# LAN9254_D_P1.net
KiCad netlist of a schematic drawn in Altium Designer
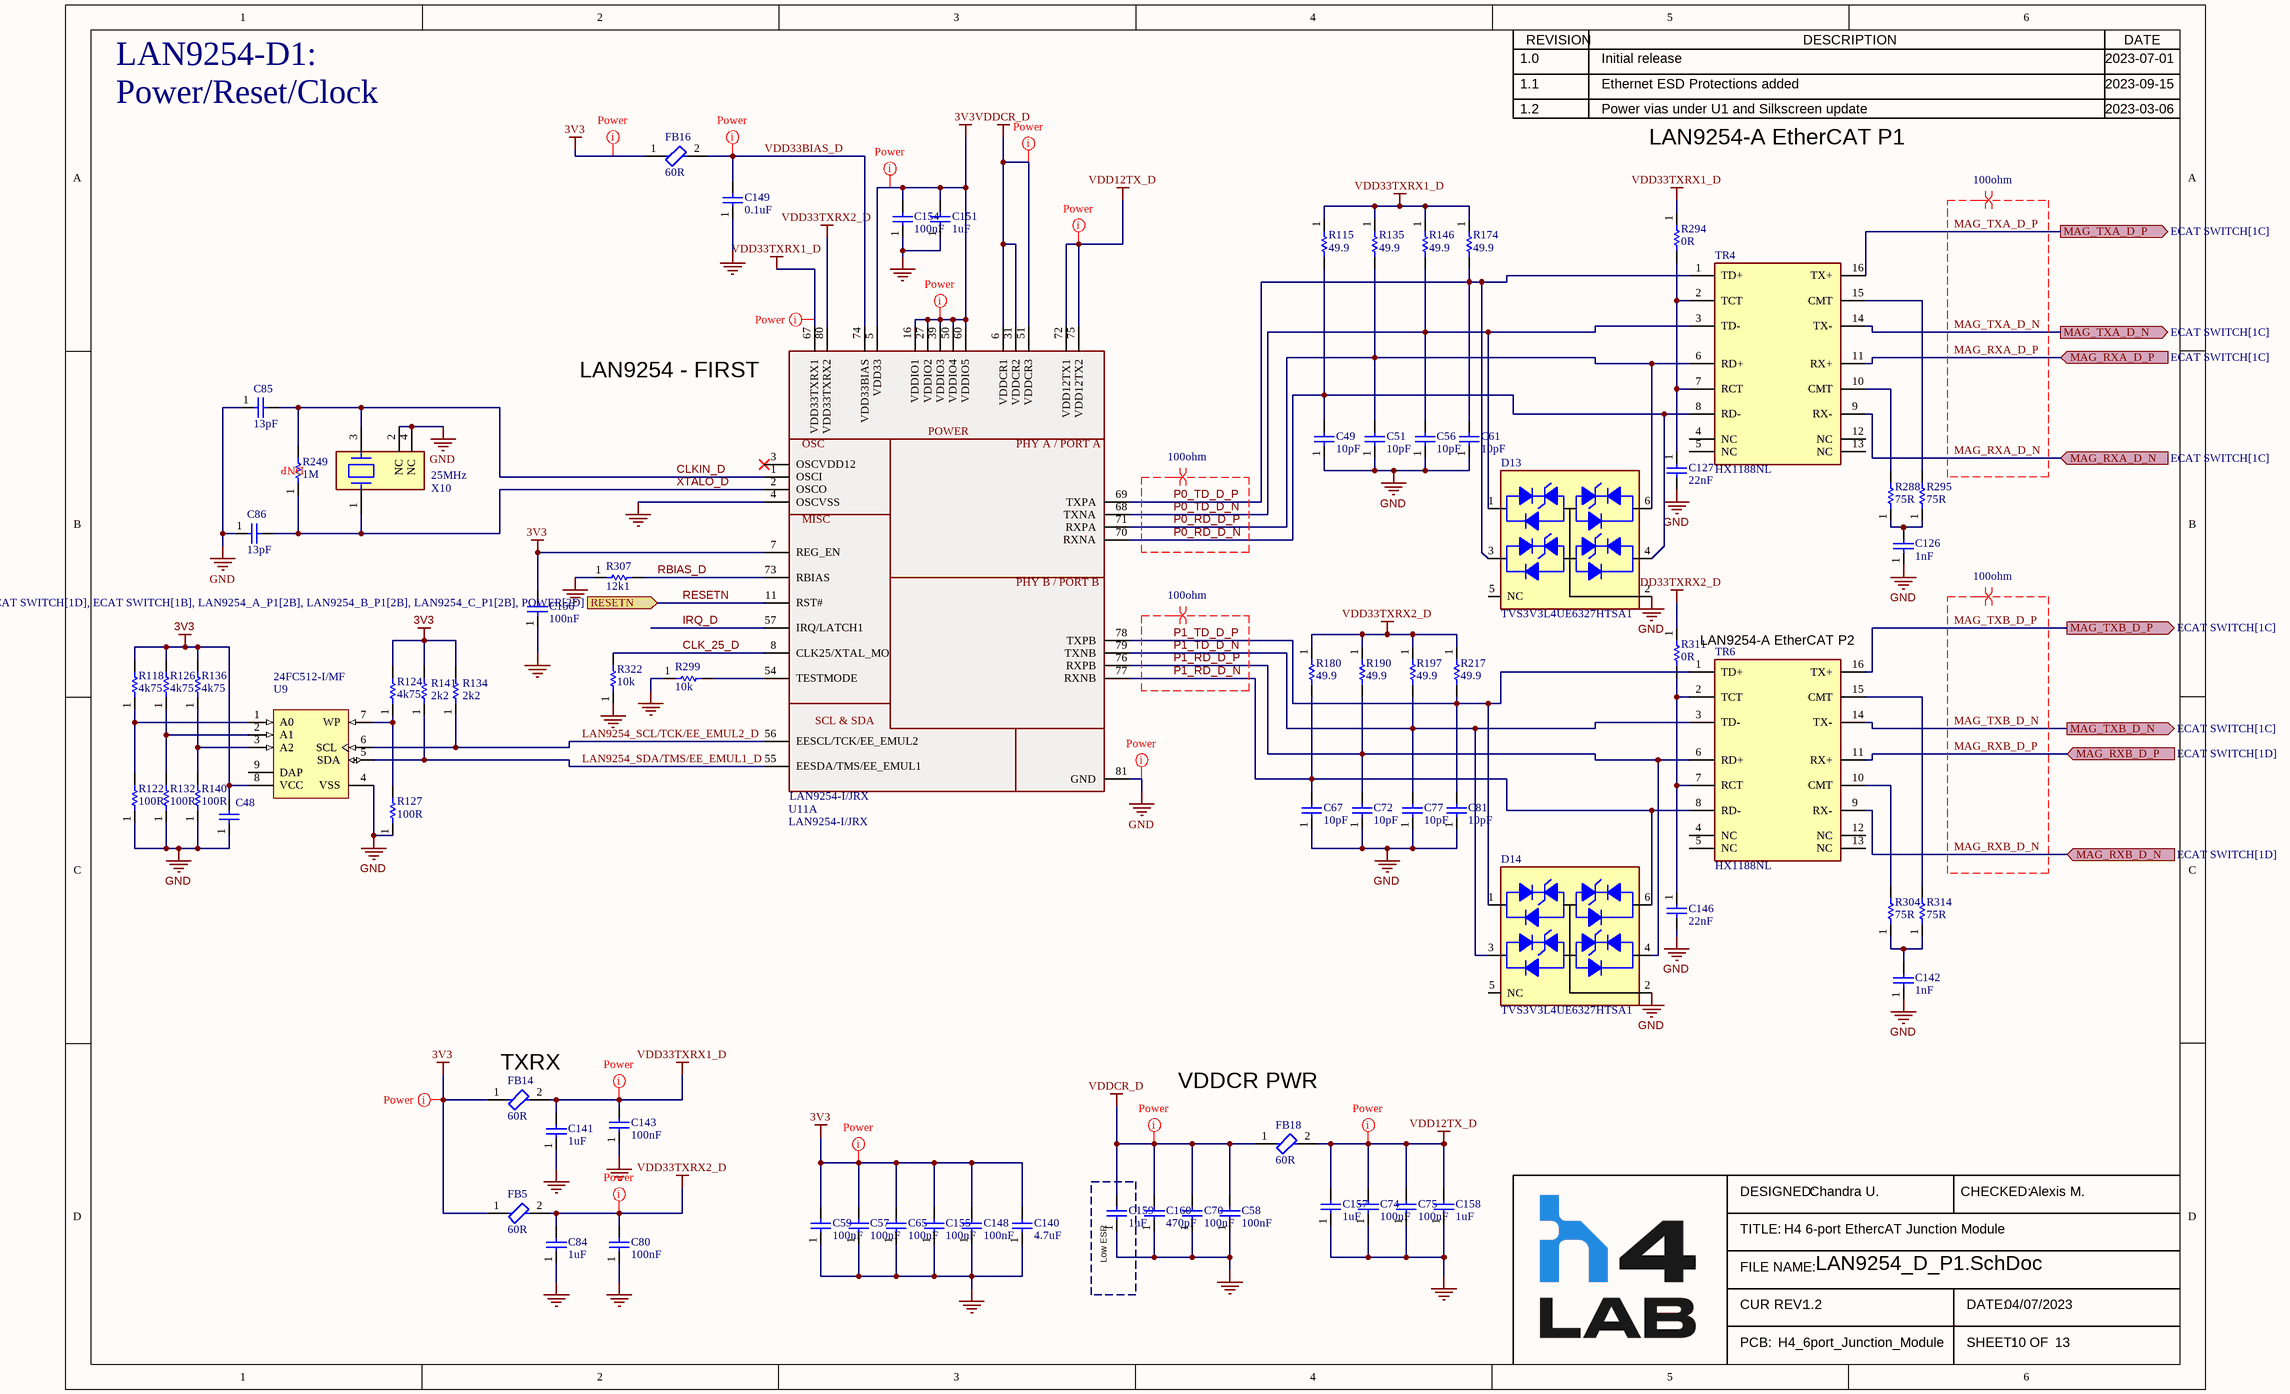
[diagram p0: LAN9254_D_P1.SchDoc]

(export (version "E")
  (design (tool "Eeschema 10.0.6"))
  (components
    (comp (ref "C48")
      (value "GRM155R71C104JA88D")
      (footprint "CAPC1005X03N(0402)")
      (description "CAP CER 0.1UF 16V X7R 0402")
      (fields (field (name "TOLERANCE") "5%"))
      (libsource (lib "IHMC_Altium_Lib") (part "100nF_16V_0402_CAP"))
    )
    (comp (ref "C49")
      (value "10pF")
      (footprint "0402_C")
      (description "Cap Ceramic 10pF 50V C0G 5% SMD 0402 125°C Punched Paper T/R")
      (fields (field (name "TOLERANCE") "5%") (field (name "MANUFACTURER") "KEMET"))
      (libsource (lib "IHMC_Altium_Lib") (part "10pF_50V_0402_C0402C100J5GAC7411"))
    )
    (comp (ref "C51")
      (value "10pF")
      (footprint "0402_C")
      (description "Cap Ceramic 10pF 50V C0G 5% SMD 0402 125°C Punched Paper T/R")
      (fields (field (name "TOLERANCE") "5%") (field (name "MANUFACTURER") "KEMET"))
      (libsource (lib "IHMC_Altium_Lib") (part "10pF_50V_0402_C0402C100J5GAC7411"))
    )
    (comp (ref "C56")
      (value "10pF")
      (footprint "0402_C")
      (description "Cap Ceramic 10pF 50V C0G 5% SMD 0402 125°C Punched Paper T/R")
      (fields (field (name "TOLERANCE") "5%") (field (name "MANUFACTURER") "KEMET"))
      (libsource (lib "IHMC_Altium_Lib") (part "10pF_50V_0402_C0402C100J5GAC7411"))
    )
    (comp (ref "C57")
      (value "100nF")
      (footprint "CAPC1005X03N(0402)")
      (description "CAP CER 0.1UF 16V X7R 0402")
      (fields (field (name "MPN") "GRM155R71C104JA88D") (field (name "TOLERANCE") "5%"))
      (libsource (lib "IHMC_Altium_Lib") (part "100nF_16V_0402_CAP"))
    )
    (comp (ref "C58")
      (value "100nF")
      (footprint "CAPC1005X03N(0402)")
      (description "CAP CER 0.1UF 16V X7R 0402")
      (fields (field (name "MPN") "GRM155R71C104JA88D") (field (name "TOLERANCE") "5%"))
      (libsource (lib "IHMC_Altium_Lib") (part "100nF_16V_0402_CAP"))
    )
    (comp (ref "C59")
      (value "100nF")
      (footprint "CAPC1005X03N(0402)")
      (description "CAP CER 0.1UF 16V X7R 0402")
      (fields (field (name "MPN") "GRM155R71C104JA88D") (field (name "TOLERANCE") "5%"))
      (libsource (lib "IHMC_Altium_Lib") (part "100nF_16V_0402_CAP"))
    )
    (comp (ref "C61")
      (value "10pF")
      (footprint "0402_C")
      (description "Cap Ceramic 10pF 50V C0G 5% SMD 0402 125°C Punched Paper T/R")
      (fields (field (name "TOLERANCE") "5%") (field (name "MANUFACTURER") "KEMET"))
      (libsource (lib "IHMC_Altium_Lib") (part "10pF_50V_0402_C0402C100J5GAC7411"))
    )
    (comp (ref "C65")
      (value "100nF")
      (footprint "CAPC1005X03N(0402)")
      (description "CAP CER 0.1UF 16V X7R 0402")
      (fields (field (name "MPN") "GRM155R71C104JA88D") (field (name "TOLERANCE") "5%"))
      (libsource (lib "IHMC_Altium_Lib") (part "100nF_16V_0402_CAP"))
    )
    (comp (ref "C67")
      (value "10pF")
      (footprint "0402_C")
      (description "Cap Ceramic 10pF 50V C0G 5% SMD 0402 125°C Punched Paper T/R")
      (fields (field (name "TOLERANCE") "5%") (field (name "MANUFACTURER") "KEMET"))
      (libsource (lib "IHMC_Altium_Lib") (part "10pF_50V_0402_C0402C100J5GAC7411"))
    )
    (comp (ref "C70")
      (value "100nF")
      (footprint "CAPC1005X03N(0402)")
      (description "CAP CER 0.1UF 16V X7R 0402")
      (fields (field (name "MPN") "GRM155R71C104JA88D") (field (name "TOLERANCE") "5%"))
      (libsource (lib "IHMC_Altium_Lib") (part "100nF_16V_0402_CAP"))
    )
    (comp (ref "C72")
      (value "10pF")
      (footprint "0402_C")
      (description "Cap Ceramic 10pF 50V C0G 5% SMD 0402 125°C Punched Paper T/R")
      (fields (field (name "TOLERANCE") "5%") (field (name "MANUFACTURER") "KEMET"))
      (libsource (lib "IHMC_Altium_Lib") (part "10pF_50V_0402_C0402C100J5GAC7411"))
    )
    (comp (ref "C74")
      (value "100nF")
      (footprint "CAPC1005X03N(0402)")
      (description "CAP CER 0.1UF 16V X7R 0402")
      (fields (field (name "MPN") "GRM155R71C104JA88D") (field (name "TOLERANCE") "5%"))
      (libsource (lib "IHMC_Altium_Lib") (part "100nF_16V_0402_CAP"))
    )
    (comp (ref "C75")
      (value "100nF")
      (footprint "CAPC1005X03N(0402)")
      (description "CAP CER 0.1UF 16V X7R 0402")
      (fields (field (name "MPN") "GRM155R71C104JA88D") (field (name "TOLERANCE") "5%"))
      (libsource (lib "IHMC_Altium_Lib") (part "100nF_16V_0402_CAP"))
    )
    (comp (ref "C77")
      (value "10pF")
      (footprint "0402_C")
      (description "Cap Ceramic 10pF 50V C0G 5% SMD 0402 125°C Punched Paper T/R")
      (fields (field (name "TOLERANCE") "5%") (field (name "MANUFACTURER") "KEMET"))
      (libsource (lib "IHMC_Altium_Lib") (part "10pF_50V_0402_C0402C100J5GAC7411"))
    )
    (comp (ref "C80")
      (value "100nF")
      (footprint "CAPC1005X03N(0402)")
      (description "CAP CER 0.1UF 16V X7R 0402")
      (fields (field (name "MPN") "GRM155R71C104JA88D") (field (name "TOLERANCE") "5%"))
      (libsource (lib "IHMC_Altium_Lib") (part "100nF_16V_0402_CAP"))
    )
    (comp (ref "C81")
      (value "10pF")
      (footprint "0402_C")
      (description "Cap Ceramic 10pF 50V C0G 5% SMD 0402 125°C Punched Paper T/R")
      (fields (field (name "TOLERANCE") "5%") (field (name "MANUFACTURER") "KEMET"))
      (libsource (lib "IHMC_Altium_Lib") (part "10pF_50V_0402_C0402C100J5GAC7411"))
    )
    (comp (ref "C84")
      (value "1uF")
      (footprint "CAPC1608X09N(0603)")
      (description "MLCC - SMD/SMT 25volts 1uF X5R 10%")
      (fields
        (field (name "MPN") "C0603C105K3PACTU")
        (field (name "VOLTAGE") "25VDC")
        (field (name "DRAWN BY") "TC")
      )
      (libsource (lib "IHMC_Altium_Lib") (part "1uF_25VDC_0603_Cap"))
    )
    (comp (ref "C85")
      (value "13pF")
      (footprint "0402_C")
      (description "Cap Ceramic Monolithic 13pF 50VDC 2% SMD Emboss T/R")
      (fields
        (field (name "MANUFACTURER") "Murata")
        (field (name "MANUFACTURER PART NUMBER") "GRM0225C1H130GA03L")
      )
      (libsource (lib "IHMC_Capacitors") (part "13pF_50V_0402_CAP_GRM0225C1H130GA03L"))
    )
    (comp (ref "C86")
      (value "13pF")
      (footprint "0402_C")
      (description "Cap Ceramic Monolithic 13pF 50VDC 2% SMD Emboss T/R")
      (fields
        (field (name "MANUFACTURER") "Murata")
        (field (name "MANUFACTURER PART NUMBER") "GRM0225C1H130GA03L")
      )
      (libsource (lib "IHMC_Capacitors") (part "13pF_50V_0402_CAP_GRM0225C1H130GA03L"))
    )
    (comp (ref "C126")
      (value "1nF")
      (footprint "CAPC3216X16N(1206)")
      (description "CAP CER 1000PF 2KV X7R 1206")
      (fields (field (name "TOLERANCE") "10%") (field (name "MPN") "CC1206KKX7RDBB102"))
      (libsource (lib "IHMC_Altium_Lib") (part "1nF_2kV_1206_CAP"))
    )
    (comp (ref "C127")
      (value "22nF")
      (footprint "CAPC1005X03N(0402)")
      (description "CAP CER 0.022UF 50V X7R 0402")
      (fields (field (name "MPN") "GCM155R71H223KA55D") (field (name "TOLERANCE") "10%"))
      (libsource (lib "IHMC_Capacitors") (part "22nF_50V_0402_CAP"))
    )
    (comp (ref "C140")
      (value "4.7uF")
      (footprint "CAPC3216X16N(1206)")
      (description "CAP CER 4.7UF 50V X7R 1206")
      (fields (field (name "MPN") "CL31B475KBHNNNE") (field (name "TOLERANCE") "10%"))
      (libsource (lib "IHMC_Altium_Lib") (part "4.7uF_50V_1206_CAP"))
    )
    (comp (ref "C141")
      (value "1uF")
      (footprint "CAPC1608X09N(0603)")
      (description "MLCC - SMD/SMT 25volts 1uF X5R 10%")
      (fields
        (field (name "MPN") "C0603C105K3PACTU")
        (field (name "VOLTAGE") "25VDC")
        (field (name "DRAWN BY") "TC")
      )
      (libsource (lib "IHMC_Altium_Lib") (part "1uF_25VDC_0603_Cap"))
    )
    (comp (ref "C142")
      (value "1nF")
      (footprint "CAPC3216X16N(1206)")
      (description "CAP CER 1000PF 2KV X7R 1206")
      (fields (field (name "TOLERANCE") "10%") (field (name "MPN") "CC1206KKX7RDBB102"))
      (libsource (lib "IHMC_Altium_Lib") (part "1nF_2kV_1206_CAP"))
    )
    (comp (ref "C143")
      (value "100nF")
      (footprint "CAPC1005X03N(0402)")
      (description "CAP CER 0.1UF 16V X7R 0402")
      (fields (field (name "MPN") "GRM155R71C104JA88D") (field (name "TOLERANCE") "5%"))
      (libsource (lib "IHMC_Altium_Lib") (part "100nF_16V_0402_CAP"))
    )
    (comp (ref "C146")
      (value "22nF")
      (footprint "CAPC1005X03N(0402)")
      (description "CAP CER 0.022UF 50V X7R 0402")
      (fields (field (name "MPN") "GCM155R71H223KA55D") (field (name "TOLERANCE") "10%"))
      (libsource (lib "IHMC_Capacitors") (part "22nF_50V_0402_CAP"))
    )
    (comp (ref "C148")
      (value "100nF")
      (footprint "CAPC1005X03N(0402)")
      (description "CAP CER 0.1UF 16V X7R 0402")
      (fields (field (name "MPN") "GRM155R71C104JA88D") (field (name "TOLERANCE") "5%"))
      (libsource (lib "IHMC_Altium_Lib") (part "100nF_16V_0402_CAP"))
    )
    (comp (ref "C149")
      (value "0.1uF")
      (footprint "CAPC1608X09N(0603)")
      (description "CAP CER 0.1UF 100V X7R 0603")
      (fields (field (name "MPN") "CL10B104KC8NNNC") (field (name "TOLERANCE") "10%"))
      (libsource (lib "IHMC_Altium_Lib") (part "0.1uF_100V_0603_CAP"))
    )
    (comp (ref "C151")
      (value "1uF")
      (footprint "0603_C")
      (description "Multilayer Ceramic Capacitors (High dielectric type), 10V, 1 uF, ± 10 %, 0603, X5R, RoHS")
      (fields (field (name "TOLERANCE") "10%") (field (name "MANUFACTURER") "Taiyo Yuden"))
      (libsource (lib "IHMC_Capacitors") (part "1uF_10V_low_ESR_0603_LMK107BJ105KA-T"))
    )
    (comp (ref "C154")
      (value "100nF")
      (footprint "CAPC1005X03N(0402)")
      (description "CAP CER 0.1UF 16V X7R 0402")
      (fields (field (name "MPN") "GRM155R71C104JA88D") (field (name "TOLERANCE") "5%"))
      (libsource (lib "IHMC_Altium_Lib") (part "100nF_16V_0402_CAP"))
    )
    (comp (ref "C155")
      (value "100nF")
      (footprint "CAPC1005X03N(0402)")
      (description "CAP CER 0.1UF 16V X7R 0402")
      (fields (field (name "MPN") "GRM155R71C104JA88D") (field (name "TOLERANCE") "5%"))
      (libsource (lib "IHMC_Altium_Lib") (part "100nF_16V_0402_CAP"))
    )
    (comp (ref "C156")
      (value "100nF")
      (footprint "CAPC1005X03N(0402)")
      (description "CAP CER 0.1UF 16V X7R 0402")
      (fields (field (name "MPN") "GRM155R71C104JA88D") (field (name "TOLERANCE") "5%"))
      (libsource (lib "IHMC_Altium_Lib") (part "100nF_16V_0402_CAP"))
    )
    (comp (ref "C157")
      (value "1uF")
      (footprint "CAPC1608X09N(0603)")
      (description "MLCC - SMD/SMT 25volts 1uF X5R 10%")
      (fields
        (field (name "MPN") "C0603C105K3PACTU")
        (field (name "VOLTAGE") "25VDC")
        (field (name "DRAWN BY") "TC")
      )
      (libsource (lib "IHMC_Altium_Lib") (part "1uF_25VDC_0603_Cap"))
    )
    (comp (ref "C158")
      (value "1uF")
      (footprint "CAPC1608X09N(0603)")
      (description "MLCC - SMD/SMT 25volts 1uF X5R 10%")
      (fields
        (field (name "MPN") "C0603C105K3PACTU")
        (field (name "VOLTAGE") "25VDC")
        (field (name "DRAWN BY") "TC")
      )
      (libsource (lib "IHMC_Altium_Lib") (part "1uF_25VDC_0603_Cap"))
    )
    (comp (ref "C159")
      (value "1uF")
      (footprint "0603_C")
      (description "Multilayer Ceramic Capacitors (High dielectric type), 10V, 1 uF, ± 10 %, 0603, X5R, RoHS")
      (fields (field (name "TOLERANCE") "10%") (field (name "MANUFACTURER") "Taiyo Yuden"))
      (libsource (lib "IHMC_Capacitors") (part "1uF_10V_low_ESR_0603_LMK107BJ105KA-T"))
    )
    (comp (ref "C160")
      (value "470pF")
      (footprint "CAPC1005X03N(0402)")
      (description "CAP CER 470PF 50V C0G/NP0 0402")
      (fields (field (name "MPN") "GCM1555C1H471JA16D") (field (name "VOLTAGE") "50V"))
      (libsource (lib "IHMC_Altium_Lib") (part "470pF_50V_0402_CAP"))
    )
    (comp (ref "D13")
      (value "TVS3V3L4UE6327HTSA1")
      (footprint "FP-SOT457-MFG")
      (description "Trans Voltage Suppressor Diode, 3.3V V(RWM), Unidirectional, 4 Element, Silicon")
      (fields (field (name "MANUFACTURER") "Infineon"))
      (libsource (lib "IHMC_Altium_Lib") (part "TVS_DIODE_ETHERCAT_PHY_7.7V_20A_TVS3V3L4UE6327HTSA1"))
    )
    (comp (ref "D14")
      (value "TVS3V3L4UE6327HTSA1")
      (footprint "FP-SOT457-MFG")
      (description "Trans Voltage Suppressor Diode, 3.3V V(RWM), Unidirectional, 4 Element, Silicon")
      (fields (field (name "MANUFACTURER") "Infineon"))
      (libsource (lib "IHMC_Altium_Lib") (part "TVS_DIODE_ETHERCAT_PHY_7.7V_20A_TVS3V3L4UE6327HTSA1"))
    )
    (comp (ref "FB5")
      (value "BKP2125HS600-T")
      (footprint "FP-BKP2125-IPC_C")
      (fields
        (field (name "TOLERANCE") "25%")
        (field (name "MANUFACTURER") "Taiyo Yuden")
        (field (name "IMPEDANCE") "60R")
      )
      (libsource (lib "IHMC_Altium_Lib") (part "60R_100Mhz_0805_3A"))
    )
    (comp (ref "FB14")
      (value "BKP2125HS600-T")
      (footprint "FP-BKP2125-IPC_C")
      (fields
        (field (name "TOLERANCE") "25%")
        (field (name "MANUFACTURER") "Taiyo Yuden")
        (field (name "IMPEDANCE") "60R")
      )
      (libsource (lib "IHMC_Altium_Lib") (part "60R_100Mhz_0805_3A"))
    )
    (comp (ref "FB16")
      (value "BKP2125HS600-T")
      (footprint "FP-BKP2125-IPC_C")
      (fields
        (field (name "TOLERANCE") "25%")
        (field (name "MANUFACTURER") "Taiyo Yuden")
        (field (name "IMPEDANCE") "60R")
      )
      (libsource (lib "IHMC_Altium_Lib") (part "60R_100Mhz_0805_3A"))
    )
    (comp (ref "FB18")
      (value "BKP2125HS600-T")
      (footprint "FP-BKP2125-IPC_C")
      (fields
        (field (name "TOLERANCE") "25%")
        (field (name "MANUFACTURER") "Taiyo Yuden")
        (field (name "IMPEDANCE") "60R")
      )
      (libsource (lib "IHMC_Altium_Lib") (part "60R_100Mhz_0805_3A"))
    )
    (comp (ref "R115")
      (value "49.9")
      (footprint "RESC1005X06N(0402)")
      (description "RES SMD 49.9 OHM 1% 1/16W 0402")
      (fields
        (field (name "MPN") "CRCW040249R9FKED")
        (field (name "TOLERANCE") "1%")
        (field (name "DRAWN BY") "TC")
      )
      (libsource (lib "IHMC_Altium_Lib") (part "49R9_1/10W_0402_RES"))
    )
    (comp (ref "R118")
      (value "4k75")
      (footprint "RESC1005X06N(0402)")
      (description "RES SMD 4.75K OHM 1% 1/16W 0402")
      (fields (field (name "MPN") "RC0402FR-074K75L") (field (name "POWER") "1/16"))
      (libsource (lib "IHMC_Altium_Lib") (part "4k75_1/16_0402_RES"))
    )
    (comp (ref "R122")
      (value "100R")
      (footprint "0402")
      (description "Res Thick Film 0402 100 Ohm 1% 0.063W(1/16W) ±200ppm/C Pad SMD Automotive T/R")
      (fields
        (field (name "MANUFACTURER") "TE Connectivity")
        (field (name "MANUFACTURER PART NUMBER") "CRGCQ0402F100R")
      )
      (libsource (lib "IHMC_Altium_Lib") (part "100R_1/16_0402_RES"))
    )
    (comp (ref "R124")
      (value "4k75")
      (footprint "RESC1005X06N(0402)")
      (description "RES SMD 4.75K OHM 1% 1/16W 0402")
      (fields (field (name "MPN") "RC0402FR-074K75L") (field (name "POWER") "1/16"))
      (libsource (lib "IHMC_Altium_Lib") (part "4k75_1/16_0402_RES"))
    )
    (comp (ref "R126")
      (value "4k75")
      (footprint "RESC1005X06N(0402)")
      (description "RES SMD 4.75K OHM 1% 1/16W 0402")
      (fields (field (name "MPN") "RC0402FR-074K75L") (field (name "POWER") "1/16"))
      (libsource (lib "IHMC_Altium_Lib") (part "4k75_1/16_0402_RES"))
    )
    (comp (ref "R127")
      (value "100R")
      (footprint "0402")
      (description "Res Thick Film 0402 100 Ohm 1% 0.063W(1/16W) ±200ppm/C Pad SMD Automotive T/R")
      (fields
        (field (name "MANUFACTURER") "TE Connectivity")
        (field (name "MANUFACTURER PART NUMBER") "CRGCQ0402F100R")
      )
      (libsource (lib "IHMC_Altium_Lib") (part "100R_1/16_0402_RES"))
    )
    (comp (ref "R132")
      (value "100R")
      (footprint "0402")
      (description "Res Thick Film 0402 100 Ohm 1% 0.063W(1/16W) ±200ppm/C Pad SMD Automotive T/R")
      (fields
        (field (name "MANUFACTURER") "TE Connectivity")
        (field (name "MANUFACTURER PART NUMBER") "CRGCQ0402F100R")
      )
      (libsource (lib "IHMC_Altium_Lib") (part "100R_1/16_0402_RES"))
    )
    (comp (ref "R134")
      (value "2k2")
      (footprint "0402")
      (description "Vishay CRCW Series Thick Film Resistor 0402 Case 2.2k 5% 0.063W 200ppm/K")
      (fields (field (name "TOLERANCE") "5%") (field (name "MANUFACTURER") "Vishay Dale"))
      (libsource (lib "IHMC_Altium_Lib") (part "2k2_1/16_0402_CRCW04022K20JNED_RES"))
    )
    (comp (ref "R135")
      (value "49.9")
      (footprint "RESC1005X06N(0402)")
      (description "RES SMD 49.9 OHM 1% 1/16W 0402")
      (fields
        (field (name "MPN") "CRCW040249R9FKED")
        (field (name "TOLERANCE") "1%")
        (field (name "DRAWN BY") "TC")
      )
      (libsource (lib "IHMC_Altium_Lib") (part "49R9_1/10W_0402_RES"))
    )
    (comp (ref "R136")
      (value "4k75")
      (footprint "RESC1005X06N(0402)")
      (description "RES SMD 4.75K OHM 1% 1/16W 0402")
      (fields (field (name "MPN") "RC0402FR-074K75L") (field (name "POWER") "1/16"))
      (libsource (lib "IHMC_Altium_Lib") (part "4k75_1/16_0402_RES"))
    )
    (comp (ref "R140")
      (value "100R")
      (footprint "0402")
      (description "Res Thick Film 0402 100 Ohm 1% 0.063W(1/16W) ±200ppm/C Pad SMD Automotive T/R")
      (fields
        (field (name "MANUFACTURER") "TE Connectivity")
        (field (name "MANUFACTURER PART NUMBER") "CRGCQ0402F100R")
      )
      (libsource (lib "IHMC_Altium_Lib") (part "100R_1/16_0402_RES"))
    )
    (comp (ref "R141")
      (value "2k2")
      (footprint "0402")
      (description "Vishay CRCW Series Thick Film Resistor 0402 Case 2.2k 5% 0.063W 200ppm/K")
      (fields (field (name "TOLERANCE") "5%") (field (name "MANUFACTURER") "Vishay Dale"))
      (libsource (lib "IHMC_Altium_Lib") (part "2k2_1/16_0402_CRCW04022K20JNED_RES"))
    )
    (comp (ref "R146")
      (value "49.9")
      (footprint "RESC1005X06N(0402)")
      (description "RES SMD 49.9 OHM 1% 1/16W 0402")
      (fields
        (field (name "MPN") "CRCW040249R9FKED")
        (field (name "TOLERANCE") "1%")
        (field (name "DRAWN BY") "TC")
      )
      (libsource (lib "IHMC_Altium_Lib") (part "49R9_1/10W_0402_RES"))
    )
    (comp (ref "R174")
      (value "49.9")
      (footprint "RESC1005X06N(0402)")
      (description "RES SMD 49.9 OHM 1% 1/16W 0402")
      (fields
        (field (name "MPN") "CRCW040249R9FKED")
        (field (name "TOLERANCE") "1%")
        (field (name "DRAWN BY") "TC")
      )
      (libsource (lib "IHMC_Altium_Lib") (part "49R9_1/10W_0402_RES"))
    )
    (comp (ref "R180")
      (value "49.9")
      (footprint "RESC1005X06N(0402)")
      (description "RES SMD 49.9 OHM 1% 1/16W 0402")
      (fields
        (field (name "MPN") "CRCW040249R9FKED")
        (field (name "TOLERANCE") "1%")
        (field (name "DRAWN BY") "TC")
      )
      (libsource (lib "IHMC_Altium_Lib") (part "49R9_1/10W_0402_RES"))
    )
    (comp (ref "R190")
      (value "49.9")
      (footprint "RESC1005X06N(0402)")
      (description "RES SMD 49.9 OHM 1% 1/16W 0402")
      (fields
        (field (name "MPN") "CRCW040249R9FKED")
        (field (name "TOLERANCE") "1%")
        (field (name "DRAWN BY") "TC")
      )
      (libsource (lib "IHMC_Altium_Lib") (part "49R9_1/10W_0402_RES"))
    )
    (comp (ref "R197")
      (value "49.9")
      (footprint "RESC1005X06N(0402)")
      (description "RES SMD 49.9 OHM 1% 1/16W 0402")
      (fields
        (field (name "MPN") "CRCW040249R9FKED")
        (field (name "TOLERANCE") "1%")
        (field (name "DRAWN BY") "TC")
      )
      (libsource (lib "IHMC_Altium_Lib") (part "49R9_1/10W_0402_RES"))
    )
    (comp (ref "R217")
      (value "49.9")
      (footprint "RESC1005X06N(0402)")
      (description "RES SMD 49.9 OHM 1% 1/16W 0402")
      (fields
        (field (name "MPN") "CRCW040249R9FKED")
        (field (name "TOLERANCE") "1%")
        (field (name "DRAWN BY") "TC")
      )
      (libsource (lib "IHMC_Altium_Lib") (part "49R9_1/10W_0402_RES"))
    )
    (comp (ref "R249")
      (value "1M")
      (footprint "RESC1608X09N(0603)")
      (description "RES SMD 1M OHM 1% 1/10W 0603")
      (fields (field (name "MPN") "RC0603FR-071ML") (field (name "TOLERANCE") "1%"))
      (libsource (lib "IHMC_Altium_Lib") (part "1M_1/10W_RES_0603"))
    )
    (comp (ref "R288")
      (value "75R")
      (footprint "RESC1005X06N(0402)")
      (description "RES SMD 75 OHM 1% 1/16W 0402")
      (fields
        (field (name "MPN") "CRCW040275R0FKEDC")
        (field (name "TOLERANCE") "+/-1%")
        (field (name "DRAWN BY") "TC")
      )
      (libsource (lib "IHMC_Altium_Lib") (part "75R_1/10W_0402_RES"))
    )
    (comp (ref "R294")
      (value "0R")
      (footprint "0402")
      (fields
        (field (name "MANUFACTURER") "Vishay Dale")
        (field (name "MANUFACTURER PART NUMBER") "RCS04020000Z0ED")
      )
      (libsource (lib "IHMC_Altium_Lib") (part "0R_1/5W_0402_RCS04020000Z0ED_RES"))
    )
    (comp (ref "R295")
      (value "75R")
      (footprint "RESC1005X06N(0402)")
      (description "RES SMD 75 OHM 1% 1/16W 0402")
      (fields
        (field (name "MPN") "CRCW040275R0FKEDC")
        (field (name "TOLERANCE") "+/-1%")
        (field (name "DRAWN BY") "TC")
      )
      (libsource (lib "IHMC_Altium_Lib") (part "75R_1/10W_0402_RES"))
    )
    (comp (ref "R299")
      (value "10k")
      (footprint "RESC1005X06N(0402)")
      (description "RES SMD 10K OHM 1% 1/16W 0402")
      (fields (field (name "TOLERANCE") "1%") (field (name "POWER") "1/16W"))
      (libsource (lib "IHMC_Resistors") (part "10k_1/16W_0402_RES"))
    )
    (comp (ref "R304")
      (value "75R")
      (footprint "RESC1005X06N(0402)")
      (description "RES SMD 75 OHM 1% 1/16W 0402")
      (fields
        (field (name "MPN") "CRCW040275R0FKEDC")
        (field (name "TOLERANCE") "+/-1%")
        (field (name "DRAWN BY") "TC")
      )
      (libsource (lib "IHMC_Altium_Lib") (part "75R_1/10W_0402_RES"))
    )
    (comp (ref "R307")
      (value "12k1")
      (footprint "RESC1005X06N(0402)")
      (description "RES SMD 12.1K OHM 1% 1/16W 0402")
      (fields (field (name "MPN") "RC0402FR-0712K1L") (field (name "TOLERANCE") "1%"))
      (libsource (lib "IHMC_Altium_Lib") (part "12k1_1/16W-0402_RES"))
    )
    (comp (ref "R311")
      (value "0R")
      (footprint "0402")
      (fields
        (field (name "MANUFACTURER") "Vishay Dale")
        (field (name "MANUFACTURER PART NUMBER") "RCS04020000Z0ED")
      )
      (libsource (lib "IHMC_Altium_Lib") (part "0R_1/5W_0402_RCS04020000Z0ED_RES"))
    )
    (comp (ref "R314")
      (value "75R")
      (footprint "RESC1005X06N(0402)")
      (description "RES SMD 75 OHM 1% 1/16W 0402")
      (fields
        (field (name "MPN") "CRCW040275R0FKEDC")
        (field (name "TOLERANCE") "+/-1%")
        (field (name "DRAWN BY") "TC")
      )
      (libsource (lib "IHMC_Altium_Lib") (part "75R_1/10W_0402_RES"))
    )
    (comp (ref "R322")
      (value "10k")
      (footprint "RESC1005X06N(0402)")
      (description "RES SMD 10K OHM 1% 1/16W 0402")
      (fields (field (name "TOLERANCE") "1%") (field (name "POWER") "1/16W"))
      (libsource (lib "IHMC_Resistors") (part "10k_1/16W_0402_RES"))
    )
    (comp (ref "TR4")
      (value "HX1188NL")
      (footprint "FP-HX1188NL-MFG")
      (description "Datacom Transformer, GENERAL PURPOSE Application(s), 1:1; 1:1")
      (fields (field (name "MANUFACTURER") "Pulse"))
      (libsource (lib "IHMC_Ethernet") (part "HX1188NL_TRANSFO_LAN_-40-85DEG"))
    )
    (comp (ref "TR6")
      (value "HX1188NL")
      (footprint "FP-HX1188NL-MFG")
      (description "Datacom Transformer, GENERAL PURPOSE Application(s), 1:1; 1:1")
      (fields (field (name "MANUFACTURER") "Pulse"))
      (libsource (lib "IHMC_Ethernet") (part "HX1188NL_TRANSFO_LAN_-40-85DEG"))
    )
    (comp (ref "U9")
      (value "24FC512-I/MF")
      (footprint "DFNS-MF8")
      (description "EEPROM Serial-2Wire 512K-bit 64K x 8 1.8V/2.5V/3.3V/5V 8-Pin DFN-S EP Tube")
      (fields (field (name "MANUFACTURER") "Microchip"))
      (libsource (lib "IHMC_Altium_Lib") (part "EEPROM_512kb_1MHz_24FC512-I/MF"))
    )
    (comp (ref "U11")
      (value "LAN9254-I/JRX")
      (footprint "QFP50P1400X1400X120-81N")
      (description "2/3-PORT Ethercat Slave Controller With 32 Digios With Integrated Ethernet Phys")
      (fields (field (name "MANUFACTURER") "Microchip"))
      (libsource (lib "IHMC_Ethernet") (part "LAN9254-I/JRX"))
    )
    (comp (ref "X10")
      (value "XRCGB25M000F3A00R0")
      (footprint "FP-XRCGB-MFG")
      (description "Crystal 25MHz ±30ppm (Tol) ±35ppm (Stability) 6pF 100Ohm Automotive 4-Pin SMD T/R")
      (fields (field (name "FREQUENCY") "25MHz") (field (name "MANUFACTURER") "Murata"))
      (libsource (lib "IHMC_Altium_Lib") (part "25MHz_Crystal_2016_35PPM_XRCGB25M000F3A00R0"))
    )
  )
  (nets
    (net (code "1") (name "/CLKIN_D") (class "Default")
      (node (ref "C85") (pin "2") (pinfunction "2_2") (pintype "passive"))
      (node (ref "R249") (pin "2") (pinfunction "2_2") (pintype "passive"))
      (node (ref "U11") (pin "1") (pinfunction "OSCI_1") (pintype "passive"))
      (node (ref "X10") (pin "3") (pintype "passive"))
    )
    (net (code "2") (name "/CLK_25_D") (class "Default")
      (node (ref "R322") (pin "2") (pinfunction "2_2") (pintype "passive"))
      (node (ref "U11") (pin "8") (pinfunction "CLK25/XTAL_MO_8") (pintype "passive"))
    )
    (net (code "3") (name "/IRQ_D") (class "Default")
      (node (ref "U11") (pin "57") (pinfunction "IRQ/LATCH1_57") (pintype "passive"))
    )
    (net (code "4") (name "/LAN9254_SCL{slash}TCK{slash}EE_EMUL2_D") (class "Default")
      (node (ref "R134") (pin "1") (pinfunction "1_1") (pintype "passive"))
      (node (ref "U11") (pin "56") (pinfunction "EESCL/TCK/EE_EMUL2_56") (pintype "passive"))
      (node (ref "U9") (pin "6") (pinfunction "SCL_6") (pintype "input"))
    )
    (net (code "5") (name "/LAN9254_SDA{slash}TMS{slash}EE_EMUL1_D") (class "Default")
      (node (ref "R141") (pin "1") (pinfunction "1_1") (pintype "passive"))
      (node (ref "U11") (pin "55") (pinfunction "EESDA/TMS/EE_EMUL1_55") (pintype "passive"))
      (node (ref "U9") (pin "5") (pinfunction "SDA_5") (pintype "bidirectional"))
    )
    (net (code "6") (name "/MAG_RXA_D_N") (class "Default")
      (node (ref "TR4") (pin "9") (pinfunction "RX-_9") (pintype "passive"))
    )
    (net (code "7") (name "/MAG_RXA_D_P") (class "Default")
      (node (ref "TR4") (pin "11") (pinfunction "RX+_11") (pintype "passive"))
    )
    (net (code "8") (name "/MAG_RXB_D_N") (class "Default")
      (node (ref "TR6") (pin "9") (pinfunction "RX-_9") (pintype "passive"))
    )
    (net (code "9") (name "/MAG_RXB_D_P") (class "Default")
      (node (ref "TR6") (pin "11") (pinfunction "RX+_11") (pintype "passive"))
    )
    (net (code "10") (name "/MAG_TXA_D_N") (class "Default")
      (node (ref "TR4") (pin "14") (pinfunction "TX-_14") (pintype "passive"))
    )
    (net (code "11") (name "/MAG_TXA_D_P") (class "Default")
      (node (ref "TR4") (pin "16") (pinfunction "TX+_16") (pintype "passive"))
    )
    (net (code "12") (name "/MAG_TXB_D_N") (class "Default")
      (node (ref "TR6") (pin "14") (pinfunction "TX-_14") (pintype "passive"))
    )
    (net (code "13") (name "/MAG_TXB_D_P") (class "Default")
      (node (ref "TR6") (pin "16") (pinfunction "TX+_16") (pintype "passive"))
    )
    (net (code "14") (name "/P0_RD_D_N") (class "Default")
      (node (ref "C49") (pin "2") (pinfunction "2_2") (pintype "passive"))
      (node (ref "D13") (pin "4") (pinfunction "4_4") (pintype "passive"))
      (node (ref "R115") (pin "2") (pinfunction "2_2") (pintype "passive"))
      (node (ref "TR4") (pin "8") (pinfunction "RD-_8") (pintype "passive"))
      (node (ref "U11") (pin "70") (pinfunction "RXNA_70") (pintype "passive"))
    )
    (net (code "15") (name "/P0_RD_D_P") (class "Default")
      (node (ref "C51") (pin "2") (pinfunction "2_2") (pintype "passive"))
      (node (ref "D13") (pin "6") (pinfunction "6_6") (pintype "passive"))
      (node (ref "R135") (pin "2") (pinfunction "2_2") (pintype "passive"))
      (node (ref "TR4") (pin "6") (pinfunction "RD+_6") (pintype "passive"))
      (node (ref "U11") (pin "71") (pinfunction "RXPA_71") (pintype "passive"))
    )
    (net (code "16") (name "/P0_TD_D_N") (class "Default")
      (node (ref "C56") (pin "2") (pinfunction "2_2") (pintype "passive"))
      (node (ref "D13") (pin "1") (pinfunction "1_1") (pintype "passive"))
      (node (ref "R146") (pin "2") (pinfunction "2_2") (pintype "passive"))
      (node (ref "TR4") (pin "3") (pinfunction "TD-_3") (pintype "passive"))
      (node (ref "U11") (pin "68") (pinfunction "TXNA_68") (pintype "passive"))
    )
    (net (code "17") (name "/P0_TD_D_P") (class "Default")
      (node (ref "C61") (pin "2") (pinfunction "2_2") (pintype "passive"))
      (node (ref "D13") (pin "3") (pinfunction "3_3") (pintype "passive"))
      (node (ref "R174") (pin "2") (pinfunction "2_2") (pintype "passive"))
      (node (ref "TR4") (pin "1") (pinfunction "TD+_1") (pintype "passive"))
      (node (ref "U11") (pin "69") (pinfunction "TXPA_69") (pintype "passive"))
    )
    (net (code "18") (name "/P1_RD_D_N") (class "Default")
      (node (ref "C67") (pin "2") (pinfunction "2_2") (pintype "passive"))
      (node (ref "D14") (pin "6") (pinfunction "6_6") (pintype "passive"))
      (node (ref "R180") (pin "2") (pinfunction "2_2") (pintype "passive"))
      (node (ref "TR6") (pin "8") (pinfunction "RD-_8") (pintype "passive"))
      (node (ref "U11") (pin "77") (pinfunction "RXNB_77") (pintype "passive"))
    )
    (net (code "19") (name "/P1_RD_D_P") (class "Default")
      (node (ref "C72") (pin "2") (pinfunction "2_2") (pintype "passive"))
      (node (ref "D14") (pin "4") (pinfunction "4_4") (pintype "passive"))
      (node (ref "R190") (pin "2") (pinfunction "2_2") (pintype "passive"))
      (node (ref "TR6") (pin "6") (pinfunction "RD+_6") (pintype "passive"))
      (node (ref "U11") (pin "76") (pinfunction "RXPB_76") (pintype "passive"))
    )
    (net (code "20") (name "/P1_TD_D_N") (class "Default")
      (node (ref "C77") (pin "2") (pinfunction "2_2") (pintype "passive"))
      (node (ref "D14") (pin "3") (pinfunction "3_3") (pintype "passive"))
      (node (ref "R197") (pin "2") (pinfunction "2_2") (pintype "passive"))
      (node (ref "TR6") (pin "3") (pinfunction "TD-_3") (pintype "passive"))
      (node (ref "U11") (pin "79") (pinfunction "TXNB_79") (pintype "passive"))
    )
    (net (code "21") (name "/P1_TD_D_P") (class "Default")
      (node (ref "C81") (pin "2") (pinfunction "2_2") (pintype "passive"))
      (node (ref "D14") (pin "1") (pinfunction "1_1") (pintype "passive"))
      (node (ref "R217") (pin "2") (pinfunction "2_2") (pintype "passive"))
      (node (ref "TR6") (pin "1") (pinfunction "TD+_1") (pintype "passive"))
      (node (ref "U11") (pin "78") (pinfunction "TXPB_78") (pintype "passive"))
    )
    (net (code "22") (name "/RBIAS_D") (class "Default")
      (node (ref "R307") (pin "2") (pinfunction "2_2") (pintype "passive"))
      (node (ref "U11") (pin "73") (pinfunction "RBIAS_73") (pintype "passive"))
    )
    (net (code "23") (name "/RESETN") (class "Default")
      (node (ref "U11") (pin "11") (pinfunction "RST#_11") (pintype "passive"))
    )
    (net (code "24") (name "/VDD33BIAS_D") (class "Default")
      (node (ref "C149") (pin "2") (pinfunction "2_2") (pintype "passive"))
      (node (ref "FB16") (pin "2") (pinfunction "2_2") (pintype "passive"))
      (node (ref "U11") (pin "74") (pinfunction "VDD33BIAS_74") (pintype "passive"))
    )
    (net (code "25") (name "/XTALO_D") (class "Default")
      (node (ref "C86") (pin "2") (pinfunction "2_2") (pintype "passive"))
      (node (ref "R249") (pin "1") (pinfunction "1_1") (pintype "passive"))
      (node (ref "U11") (pin "2") (pinfunction "OSCO_2") (pintype "passive"))
      (node (ref "X10") (pin "1") (pintype "passive"))
    )
    (net (code "26") (name "3V3") (class "Default")
      (node (ref "C140") (pin "2") (pinfunction "2_2") (pintype "passive"))
      (node (ref "C148") (pin "2") (pinfunction "2_2") (pintype "passive"))
      (node (ref "C151") (pin "2") (pinfunction "2_2") (pintype "passive"))
      (node (ref "C154") (pin "2") (pinfunction "2_2") (pintype "passive"))
      (node (ref "C155") (pin "2") (pinfunction "2_2") (pintype "passive"))
      (node (ref "C156") (pin "2") (pinfunction "2_2") (pintype "passive"))
      (node (ref "C48") (pin "2") (pinfunction "2_2") (pintype "passive"))
      (node (ref "C57") (pin "2") (pinfunction "2_2") (pintype "passive"))
      (node (ref "C59") (pin "2") (pinfunction "2_2") (pintype "passive"))
      (node (ref "C65") (pin "2") (pinfunction "2_2") (pintype "passive"))
      (node (ref "FB14") (pin "1") (pinfunction "1_1") (pintype "passive"))
      (node (ref "FB16") (pin "1") (pinfunction "1_1") (pintype "passive"))
      (node (ref "FB5") (pin "1") (pinfunction "1_1") (pintype "passive"))
      (node (ref "R118") (pin "2") (pinfunction "2_2") (pintype "passive"))
      (node (ref "R124") (pin "2") (pinfunction "2_2") (pintype "passive"))
      (node (ref "R126") (pin "2") (pinfunction "2_2") (pintype "passive"))
      (node (ref "R134") (pin "2") (pinfunction "2_2") (pintype "passive"))
      (node (ref "R136") (pin "2") (pinfunction "2_2") (pintype "passive"))
      (node (ref "R141") (pin "2") (pinfunction "2_2") (pintype "passive"))
      (node (ref "U11") (pin "16") (pinfunction "VDDIO1_16") (pintype "passive"))
      (node (ref "U11") (pin "27") (pinfunction "VDDIO2_27") (pintype "passive"))
      (node (ref "U11") (pin "39") (pinfunction "VDDIO3_39") (pintype "passive"))
      (node (ref "U11") (pin "5") (pinfunction "VDD33_5") (pintype "passive"))
      (node (ref "U11") (pin "50") (pinfunction "VDDIO4_50") (pintype "passive"))
      (node (ref "U11") (pin "60") (pinfunction "VDDIO5_60") (pintype "passive"))
      (node (ref "U11") (pin "7") (pinfunction "REG_EN_7") (pintype "passive"))
      (node (ref "U9") (pin "8") (pinfunction "VCC_8") (pintype "power_in"))
    )
    (net (code "27") (name "GND") (class "Default")
      (node (ref "C126") (pin "1") (pinfunction "1_1") (pintype "passive"))
      (node (ref "C127") (pin "2") (pinfunction "2_2") (pintype "passive"))
      (node (ref "C140") (pin "1") (pinfunction "1_1") (pintype "passive"))
      (node (ref "C141") (pin "1") (pinfunction "1_1") (pintype "passive"))
      (node (ref "C142") (pin "1") (pinfunction "1_1") (pintype "passive"))
      (node (ref "C143") (pin "1") (pinfunction "1_1") (pintype "passive"))
      (node (ref "C146") (pin "2") (pinfunction "2_2") (pintype "passive"))
      (node (ref "C148") (pin "1") (pinfunction "1_1") (pintype "passive"))
      (node (ref "C149") (pin "1") (pinfunction "1_1") (pintype "passive"))
      (node (ref "C151") (pin "1") (pinfunction "1_1") (pintype "passive"))
      (node (ref "C154") (pin "1") (pinfunction "1_1") (pintype "passive"))
      (node (ref "C155") (pin "1") (pinfunction "1_1") (pintype "passive"))
      (node (ref "C156") (pin "1") (pinfunction "1_1") (pintype "passive"))
      (node (ref "C157") (pin "1") (pinfunction "1_1") (pintype "passive"))
      (node (ref "C158") (pin "1") (pinfunction "1_1") (pintype "passive"))
      (node (ref "C159") (pin "1") (pinfunction "1_1") (pintype "passive"))
      (node (ref "C160") (pin "1") (pinfunction "1_1") (pintype "passive"))
      (node (ref "C48") (pin "1") (pinfunction "1_1") (pintype "passive"))
      (node (ref "C49") (pin "1") (pinfunction "1_1") (pintype "passive"))
      (node (ref "C51") (pin "1") (pinfunction "1_1") (pintype "passive"))
      (node (ref "C56") (pin "1") (pinfunction "1_1") (pintype "passive"))
      (node (ref "C57") (pin "1") (pinfunction "1_1") (pintype "passive"))
      (node (ref "C58") (pin "1") (pinfunction "1_1") (pintype "passive"))
      (node (ref "C59") (pin "1") (pinfunction "1_1") (pintype "passive"))
      (node (ref "C61") (pin "1") (pinfunction "1_1") (pintype "passive"))
      (node (ref "C65") (pin "1") (pinfunction "1_1") (pintype "passive"))
      (node (ref "C67") (pin "1") (pinfunction "1_1") (pintype "passive"))
      (node (ref "C70") (pin "1") (pinfunction "1_1") (pintype "passive"))
      (node (ref "C72") (pin "1") (pinfunction "1_1") (pintype "passive"))
      (node (ref "C74") (pin "1") (pinfunction "1_1") (pintype "passive"))
      (node (ref "C75") (pin "1") (pinfunction "1_1") (pintype "passive"))
      (node (ref "C77") (pin "1") (pinfunction "1_1") (pintype "passive"))
      (node (ref "C80") (pin "1") (pinfunction "1_1") (pintype "passive"))
      (node (ref "C81") (pin "1") (pinfunction "1_1") (pintype "passive"))
      (node (ref "C84") (pin "1") (pinfunction "1_1") (pintype "passive"))
      (node (ref "C85") (pin "1") (pinfunction "1_1") (pintype "passive"))
      (node (ref "C86") (pin "1") (pinfunction "1_1") (pintype "passive"))
      (node (ref "D13") (pin "2") (pinfunction "GND_2") (pintype "power_in"))
      (node (ref "D14") (pin "2") (pinfunction "GND_2") (pintype "power_in"))
      (node (ref "R122") (pin "1") (pinfunction "1_1") (pintype "passive"))
      (node (ref "R127") (pin "1") (pinfunction "1_1") (pintype "passive"))
      (node (ref "R132") (pin "1") (pinfunction "1_1") (pintype "passive"))
      (node (ref "R140") (pin "1") (pinfunction "1_1") (pintype "passive"))
      (node (ref "R299") (pin "1") (pinfunction "1_1") (pintype "passive"))
      (node (ref "R307") (pin "1") (pinfunction "1_1") (pintype "passive"))
      (node (ref "R322") (pin "1") (pinfunction "1_1") (pintype "passive"))
      (node (ref "U11") (pin "4") (pinfunction "OSCVSS_4") (pintype "passive"))
      (node (ref "U11") (pin "81") (pinfunction "GND_81") (pintype "passive"))
      (node (ref "U9") (pin "4") (pinfunction "VSS_4") (pintype "power_in"))
      (node (ref "X10") (pin "2") (pinfunction "NC_2") (pintype "passive"))
      (node (ref "X10") (pin "4") (pinfunction "NC_4") (pintype "passive"))
    )
    (net (code "28") (name "Net-(C126-Pad2)") (class "Default")
      (node (ref "C126") (pin "2") (pinfunction "2_2") (pintype "passive"))
      (node (ref "R288") (pin "1") (pinfunction "1_1") (pintype "passive"))
      (node (ref "R295") (pin "1") (pinfunction "1_1") (pintype "passive"))
    )
    (net (code "29") (name "Net-(C142-Pad2)") (class "Default")
      (node (ref "C142") (pin "2") (pinfunction "2_2") (pintype "passive"))
      (node (ref "R304") (pin "1") (pinfunction "1_1") (pintype "passive"))
      (node (ref "R314") (pin "1") (pinfunction "1_1") (pintype "passive"))
    )
    (net (code "30") (name "Net-(R288-Pad2)") (class "Default")
      (node (ref "R288") (pin "2") (pinfunction "2_2") (pintype "passive"))
      (node (ref "TR4") (pin "10") (pinfunction "CMT_10") (pintype "passive"))
    )
    (net (code "31") (name "Net-(R295-Pad2)") (class "Default")
      (node (ref "R295") (pin "2") (pinfunction "2_2") (pintype "passive"))
      (node (ref "TR4") (pin "15") (pinfunction "CMT_15") (pintype "passive"))
    )
    (net (code "32") (name "Net-(R304-Pad2)") (class "Default")
      (node (ref "R304") (pin "2") (pinfunction "2_2") (pintype "passive"))
      (node (ref "TR6") (pin "10") (pinfunction "CMT_10") (pintype "passive"))
    )
    (net (code "33") (name "Net-(R314-Pad2)") (class "Default")
      (node (ref "R314") (pin "2") (pinfunction "2_2") (pintype "passive"))
      (node (ref "TR6") (pin "15") (pinfunction "CMT_15") (pintype "passive"))
    )
    (net (code "34") (name "Net-(TR4-RCT)") (class "Default")
      (node (ref "C127") (pin "1") (pinfunction "1_1") (pintype "passive"))
      (node (ref "R294") (pin "2") (pinfunction "2_2") (pintype "passive"))
      (node (ref "TR4") (pin "2") (pinfunction "TCT_2") (pintype "passive"))
      (node (ref "TR4") (pin "7") (pinfunction "RCT_7") (pintype "passive"))
    )
    (net (code "35") (name "Net-(TR6-RCT)") (class "Default")
      (node (ref "C146") (pin "1") (pinfunction "1_1") (pintype "passive"))
      (node (ref "R311") (pin "2") (pinfunction "2_2") (pintype "passive"))
      (node (ref "TR6") (pin "2") (pinfunction "TCT_2") (pintype "passive"))
      (node (ref "TR6") (pin "7") (pinfunction "RCT_7") (pintype "passive"))
    )
    (net (code "36") (name "Net-(U9-A0)") (class "Default")
      (node (ref "R118") (pin "1") (pinfunction "1_1") (pintype "passive"))
      (node (ref "R122") (pin "2") (pinfunction "2_2") (pintype "passive"))
      (node (ref "U9") (pin "1") (pinfunction "A0_1") (pintype "input"))
    )
    (net (code "37") (name "Net-(U9-A1)") (class "Default")
      (node (ref "R126") (pin "1") (pinfunction "1_1") (pintype "passive"))
      (node (ref "R132") (pin "2") (pinfunction "2_2") (pintype "passive"))
      (node (ref "U9") (pin "2") (pinfunction "A1_2") (pintype "input"))
    )
    (net (code "38") (name "Net-(U9-A2)") (class "Default")
      (node (ref "R136") (pin "1") (pinfunction "1_1") (pintype "passive"))
      (node (ref "R140") (pin "2") (pinfunction "2_2") (pintype "passive"))
      (node (ref "U9") (pin "3") (pinfunction "A2_3") (pintype "input"))
    )
    (net (code "39") (name "Net-(U9-WP)") (class "Default")
      (node (ref "R124") (pin "1") (pinfunction "1_1") (pintype "passive"))
      (node (ref "R127") (pin "2") (pinfunction "2_2") (pintype "passive"))
      (node (ref "U9") (pin "7") (pinfunction "WP_7") (pintype "input"))
    )
    (net (code "40") (name "Net-(U11A-TESTMODE)") (class "Default")
      (node (ref "R299") (pin "2") (pinfunction "2_2") (pintype "passive"))
      (node (ref "U11") (pin "54") (pinfunction "TESTMODE_54") (pintype "passive"))
    )
    (net (code "41") (name "VDD12TX_D") (class "Default")
      (node (ref "C157") (pin "2") (pinfunction "2_2") (pintype "passive"))
      (node (ref "C158") (pin "2") (pinfunction "2_2") (pintype "passive"))
      (node (ref "C74") (pin "2") (pinfunction "2_2") (pintype "passive"))
      (node (ref "C75") (pin "2") (pinfunction "2_2") (pintype "passive"))
      (node (ref "FB18") (pin "2") (pinfunction "2_2") (pintype "passive"))
      (node (ref "U11") (pin "72") (pinfunction "VDD12TX1_72") (pintype "passive"))
      (node (ref "U11") (pin "75") (pinfunction "VDD12TX2_75") (pintype "passive"))
    )
    (net (code "42") (name "VDD33TXRX1_D") (class "Default")
      (node (ref "C141") (pin "2") (pinfunction "2_2") (pintype "passive"))
      (node (ref "C143") (pin "2") (pinfunction "2_2") (pintype "passive"))
      (node (ref "FB14") (pin "2") (pinfunction "2_2") (pintype "passive"))
      (node (ref "R115") (pin "1") (pinfunction "1_1") (pintype "passive"))
      (node (ref "R135") (pin "1") (pinfunction "1_1") (pintype "passive"))
      (node (ref "R146") (pin "1") (pinfunction "1_1") (pintype "passive"))
      (node (ref "R174") (pin "1") (pinfunction "1_1") (pintype "passive"))
      (node (ref "R294") (pin "1") (pinfunction "1_1") (pintype "passive"))
      (node (ref "U11") (pin "67") (pinfunction "VDD33TXRX1_67") (pintype "passive"))
    )
    (net (code "43") (name "VDD33TXRX2_D") (class "Default")
      (node (ref "C80") (pin "2") (pinfunction "2_2") (pintype "passive"))
      (node (ref "C84") (pin "2") (pinfunction "2_2") (pintype "passive"))
      (node (ref "FB5") (pin "2") (pinfunction "2_2") (pintype "passive"))
      (node (ref "R180") (pin "1") (pinfunction "1_1") (pintype "passive"))
      (node (ref "R190") (pin "1") (pinfunction "1_1") (pintype "passive"))
      (node (ref "R197") (pin "1") (pinfunction "1_1") (pintype "passive"))
      (node (ref "R217") (pin "1") (pinfunction "1_1") (pintype "passive"))
      (node (ref "R311") (pin "1") (pinfunction "1_1") (pintype "passive"))
      (node (ref "U11") (pin "80") (pinfunction "VDD33TXRX2_80") (pintype "passive"))
    )
    (net (code "44") (name "VDDCR_D") (class "Default")
      (node (ref "C159") (pin "2") (pinfunction "2_2") (pintype "passive"))
      (node (ref "C160") (pin "2") (pinfunction "2_2") (pintype "passive"))
      (node (ref "C58") (pin "2") (pinfunction "2_2") (pintype "passive"))
      (node (ref "C70") (pin "2") (pinfunction "2_2") (pintype "passive"))
      (node (ref "FB18") (pin "1") (pinfunction "1_1") (pintype "passive"))
      (node (ref "U11") (pin "31") (pinfunction "VDDCR2_31") (pintype "passive"))
      (node (ref "U11") (pin "51") (pinfunction "VDDCR3_51") (pintype "passive"))
      (node (ref "U11") (pin "6") (pinfunction "VDDCR1_6") (pintype "passive"))
    )
    (net (code "45") (name "unconnected-(D13-NC-Pad5)") (class "Default")
      (node (ref "D13") (pin "5") (pinfunction "NC_5") (pintype "passive"))
    )
    (net (code "46") (name "unconnected-(D14-NC-Pad5)") (class "Default")
      (node (ref "D14") (pin "5") (pinfunction "NC_5") (pintype "passive"))
    )
    (net (code "47") (name "unconnected-(TR4-NC-Pad4)") (class "Default")
      (node (ref "TR4") (pin "4") (pinfunction "NC_4") (pintype "passive"))
    )
    (net (code "48") (name "unconnected-(TR4-NC-Pad5)") (class "Default")
      (node (ref "TR4") (pin "5") (pinfunction "NC_5") (pintype "passive"))
    )
    (net (code "49") (name "unconnected-(TR4-NC-Pad12)") (class "Default")
      (node (ref "TR4") (pin "12") (pinfunction "NC_12") (pintype "passive"))
    )
    (net (code "50") (name "unconnected-(TR4-NC-Pad13)") (class "Default")
      (node (ref "TR4") (pin "13") (pinfunction "NC_13") (pintype "passive"))
    )
    (net (code "51") (name "unconnected-(TR6-NC-Pad4)") (class "Default")
      (node (ref "TR6") (pin "4") (pinfunction "NC_4") (pintype "passive"))
    )
    (net (code "52") (name "unconnected-(TR6-NC-Pad5)") (class "Default")
      (node (ref "TR6") (pin "5") (pinfunction "NC_5") (pintype "passive"))
    )
    (net (code "53") (name "unconnected-(TR6-NC-Pad12)") (class "Default")
      (node (ref "TR6") (pin "12") (pinfunction "NC_12") (pintype "passive"))
    )
    (net (code "54") (name "unconnected-(TR6-NC-Pad13)") (class "Default")
      (node (ref "TR6") (pin "13") (pinfunction "NC_13") (pintype "passive"))
    )
    (net (code "55") (name "unconnected-(U9-DAP-Pad9)") (class "Default")
      (node (ref "U9") (pin "9") (pinfunction "DAP_9") (pintype "power_in"))
    )
    (net (code "56") (name "unconnected-(U11A-OSCVDD12-Pad3)") (class "Default")
      (node (ref "U11") (pin "3") (pinfunction "OSCVDD12_3") (pintype "passive+no_connect"))
    )
  )
)
